# IEEE_EXT_Base.net
KiCad netlist of a schematic drawn in EAGLE
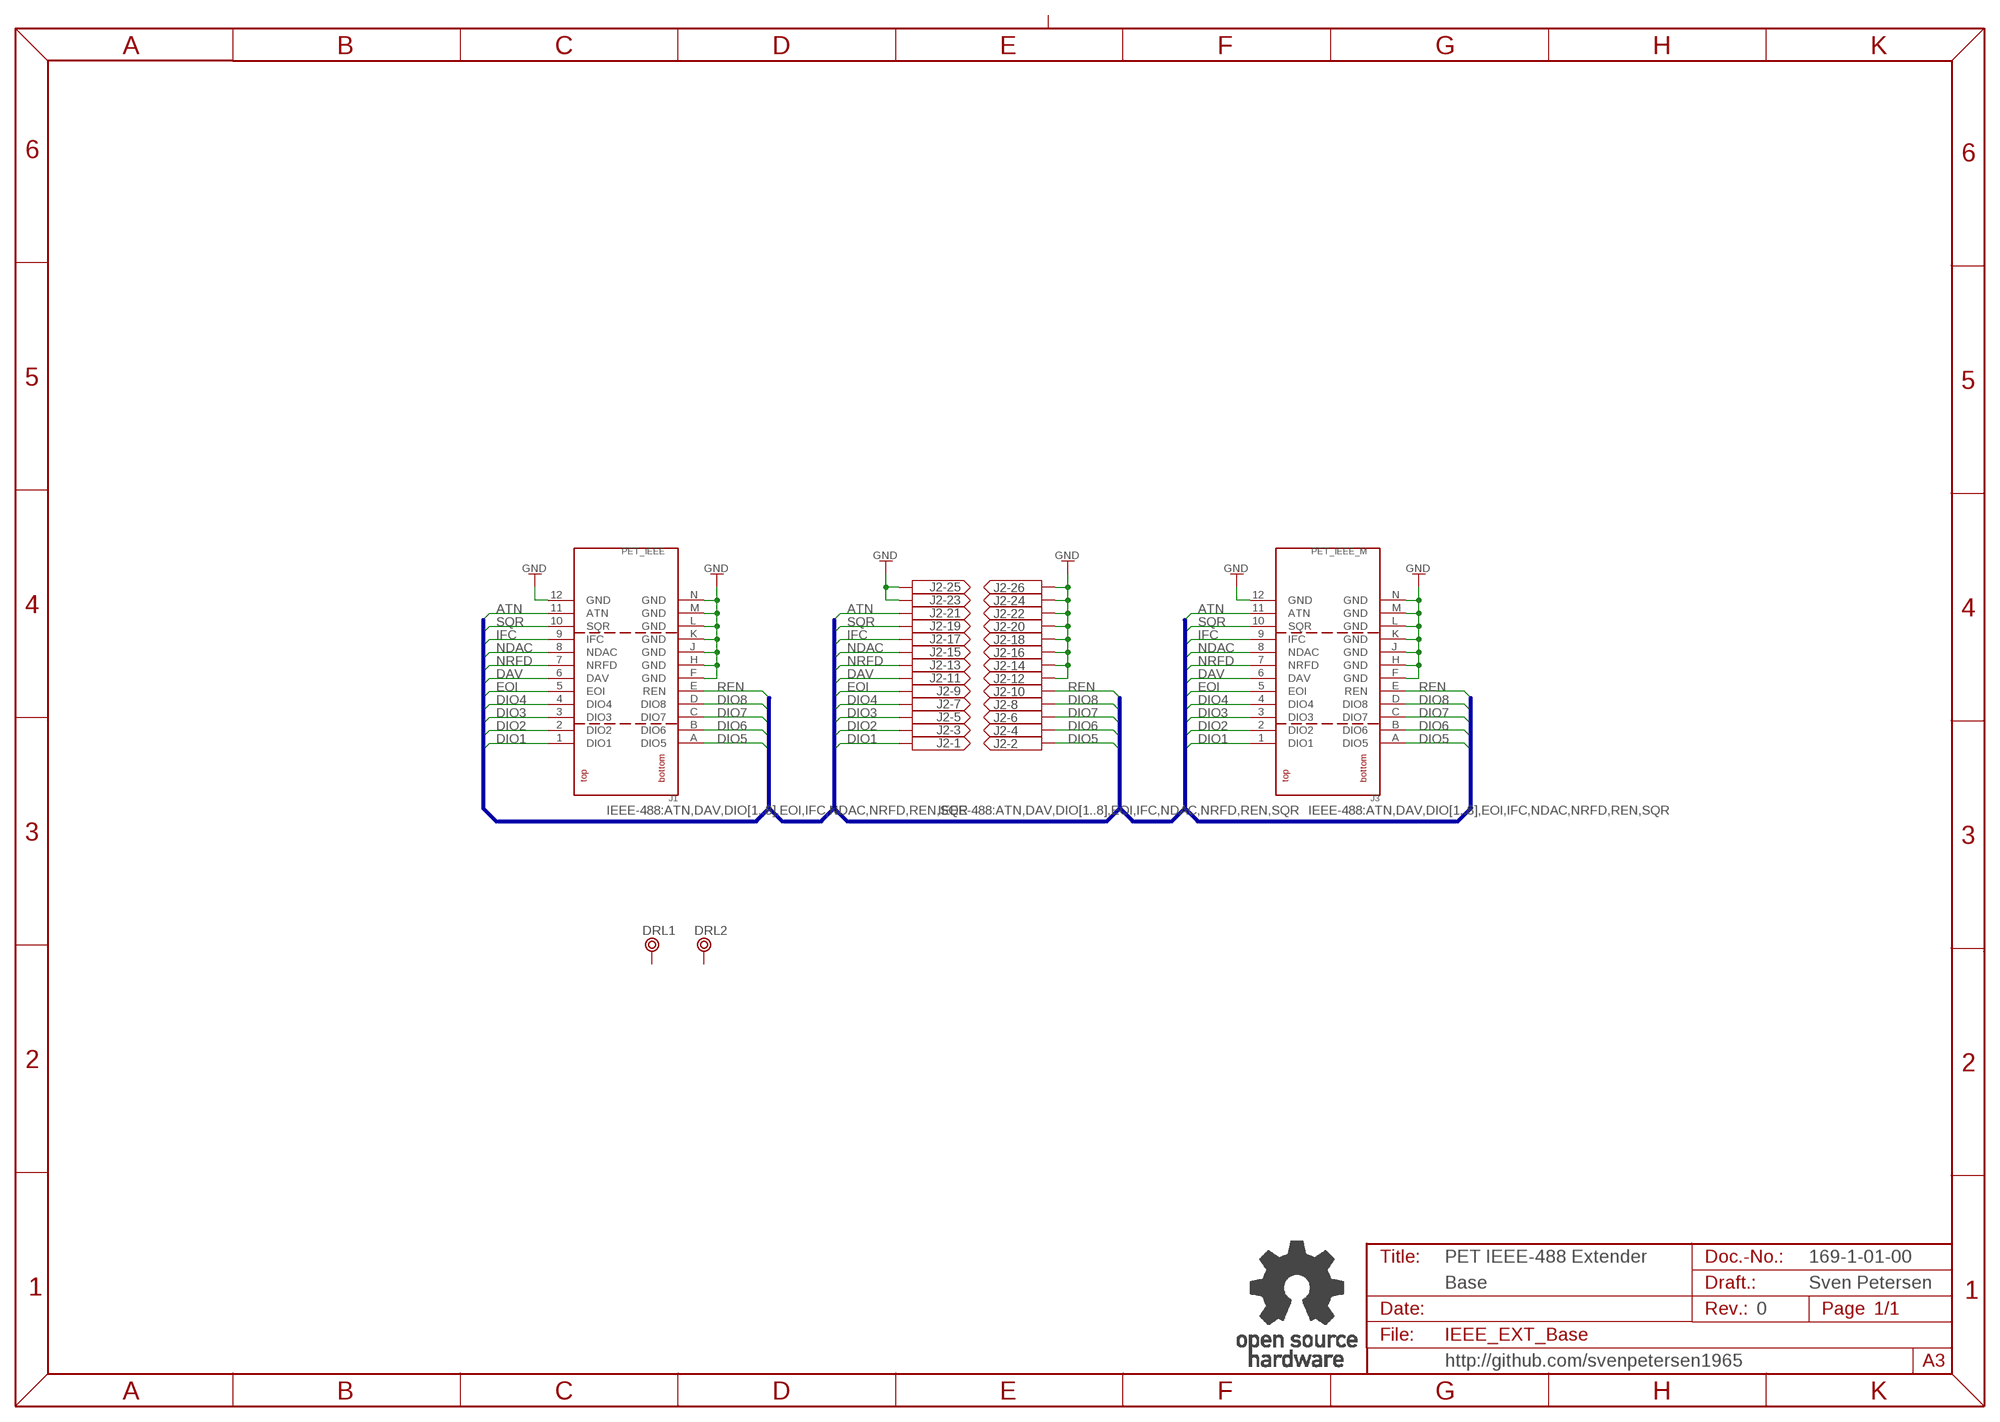
[diagram p0: schematic, sheet 1]

(export (version "E")
  (design (tool "Eeschema 10.0.6"))
  (components
    (comp (ref "DRL1")
      (value "BOHR3,5")
      (footprint "eagle-import:BOHR3,5")
      (libsource (lib "eagle-import") (part "BOHR3,5"))
    )
    (comp (ref "DRL2")
      (value "BOHR3,5")
      (footprint "eagle-import:BOHR3,5")
      (libsource (lib "eagle-import") (part "BOHR3,5"))
    )
    (comp (ref "J1")
      (value "PET_IEEE")
      (footprint "eagle-import:USERPORT")
      (libsource (lib "eagle-import") (part "PET_IEEE"))
    )
    (comp (ref "J2")
      (value "2X13WANNE")
      (footprint "eagle-import:2X13WV")
      (libsource (lib "eagle-import") (part "2X13WANNE"))
    )
    (comp (ref "J3")
      (value "PET_IEEE_M")
      (footprint "eagle-import:PET_IEEE_M")
      (libsource (lib "eagle-import") (part "PET_IEEE_M"))
    )
    (comp (ref "U$9")
      (value "OPEN_SOURCE_HW")
      (footprint "eagle-import:OPENHW")
      (libsource (lib "eagle-import") (part "OPEN_SOURCE_HW"))
    )
  )
  (nets
    (net (code "2") (name "/ATN") (class "Default")
      (node (ref "J1") (pin "11") (pinfunction "ATN_11") (pintype "output"))
      (node (ref "J2") (pin "21") (pinfunction "1_21") (pintype "bidirectional"))
      (node (ref "J3") (pin "11") (pinfunction "ATN_11") (pintype "output"))
    )
    (net (code "3") (name "/DAV") (class "Default")
      (node (ref "J1") (pin "6") (pinfunction "DAV_6") (pintype "bidirectional"))
      (node (ref "J2") (pin "11") (pinfunction "1_11") (pintype "bidirectional"))
      (node (ref "J3") (pin "6") (pinfunction "DAV_6") (pintype "bidirectional"))
    )
    (net (code "4") (name "/DIO1") (class "Default")
      (node (ref "J1") (pin "1") (pinfunction "DIO1_1") (pintype "bidirectional"))
      (node (ref "J2") (pin "1") (pinfunction "1_1") (pintype "bidirectional"))
      (node (ref "J3") (pin "1") (pinfunction "DIO1_1") (pintype "bidirectional"))
    )
    (net (code "5") (name "/DIO2") (class "Default")
      (node (ref "J1") (pin "2") (pinfunction "DIO2_2") (pintype "bidirectional"))
      (node (ref "J2") (pin "3") (pinfunction "1_3") (pintype "bidirectional"))
      (node (ref "J3") (pin "2") (pinfunction "DIO2_2") (pintype "bidirectional"))
    )
    (net (code "6") (name "/DIO3") (class "Default")
      (node (ref "J1") (pin "3") (pinfunction "DIO3_3") (pintype "bidirectional"))
      (node (ref "J2") (pin "5") (pinfunction "1_5") (pintype "bidirectional"))
      (node (ref "J3") (pin "3") (pinfunction "DIO3_3") (pintype "bidirectional"))
    )
    (net (code "7") (name "/DIO4") (class "Default")
      (node (ref "J1") (pin "4") (pinfunction "DIO4_4") (pintype "bidirectional"))
      (node (ref "J2") (pin "7") (pinfunction "1_7") (pintype "bidirectional"))
      (node (ref "J3") (pin "4") (pinfunction "DIO4_4") (pintype "bidirectional"))
    )
    (net (code "8") (name "/DIO5") (class "Default")
      (node (ref "J1") (pin "A") (pinfunction "DIO5_A") (pintype "bidirectional"))
      (node (ref "J2") (pin "2") (pinfunction "1_2") (pintype "bidirectional"))
      (node (ref "J3") (pin "A") (pinfunction "DIO5_A") (pintype "bidirectional"))
    )
    (net (code "9") (name "/DIO6") (class "Default")
      (node (ref "J1") (pin "B") (pinfunction "DIO6_B") (pintype "bidirectional"))
      (node (ref "J2") (pin "4") (pinfunction "1_4") (pintype "bidirectional"))
      (node (ref "J3") (pin "B") (pinfunction "DIO6_B") (pintype "bidirectional"))
    )
    (net (code "10") (name "/DIO7") (class "Default")
      (node (ref "J1") (pin "C") (pinfunction "DIO7_C") (pintype "bidirectional"))
      (node (ref "J2") (pin "6") (pinfunction "1_6") (pintype "bidirectional"))
      (node (ref "J3") (pin "C") (pinfunction "DIO7_C") (pintype "bidirectional"))
    )
    (net (code "11") (name "/DIO8") (class "Default")
      (node (ref "J1") (pin "D") (pinfunction "DIO8_D") (pintype "bidirectional"))
      (node (ref "J2") (pin "8") (pinfunction "1_8") (pintype "bidirectional"))
      (node (ref "J3") (pin "D") (pinfunction "DIO8_D") (pintype "bidirectional"))
    )
    (net (code "12") (name "/EOI") (class "Default")
      (node (ref "J1") (pin "5") (pinfunction "EOI_5") (pintype "input"))
      (node (ref "J2") (pin "9") (pinfunction "1_9") (pintype "bidirectional"))
      (node (ref "J3") (pin "5") (pinfunction "EOI_5") (pintype "input"))
    )
    (net (code "13") (name "/IFC") (class "Default")
      (node (ref "J1") (pin "9") (pinfunction "IFC_9") (pintype "bidirectional"))
      (node (ref "J2") (pin "17") (pinfunction "1_17") (pintype "bidirectional"))
      (node (ref "J3") (pin "9") (pinfunction "IFC_9") (pintype "bidirectional"))
    )
    (net (code "14") (name "/NDAC") (class "Default")
      (node (ref "J1") (pin "8") (pinfunction "NDAC_8") (pintype "bidirectional"))
      (node (ref "J2") (pin "15") (pinfunction "1_15") (pintype "bidirectional"))
      (node (ref "J3") (pin "8") (pinfunction "NDAC_8") (pintype "bidirectional"))
    )
    (net (code "15") (name "/NRFD") (class "Default")
      (node (ref "J1") (pin "7") (pinfunction "NRFD_7") (pintype "bidirectional"))
      (node (ref "J2") (pin "13") (pinfunction "1_13") (pintype "bidirectional"))
      (node (ref "J3") (pin "7") (pinfunction "NRFD_7") (pintype "bidirectional"))
    )
    (net (code "16") (name "/REN") (class "Default")
      (node (ref "J1") (pin "E") (pinfunction "REN_E") (pintype "bidirectional"))
      (node (ref "J2") (pin "10") (pinfunction "1_10") (pintype "bidirectional"))
      (node (ref "J3") (pin "E") (pinfunction "REN_E") (pintype "bidirectional"))
    )
    (net (code "17") (name "/SQR") (class "Default")
      (node (ref "J1") (pin "10") (pinfunction "SQR_10") (pintype "bidirectional"))
      (node (ref "J2") (pin "19") (pinfunction "1_19") (pintype "bidirectional"))
      (node (ref "J3") (pin "10") (pinfunction "SQR_10") (pintype "bidirectional"))
    )
    (net (code "19") (name "GND") (class "Default")
      (node (ref "J1") (pin "12") (pinfunction "GND_12") (pintype "power_in"))
      (node (ref "J1") (pin "F") (pinfunction "GND_F") (pintype "power_in"))
      (node (ref "J1") (pin "H") (pinfunction "GND_H") (pintype "power_in"))
      (node (ref "J1") (pin "J") (pinfunction "GND_J") (pintype "power_in"))
      (node (ref "J1") (pin "K") (pinfunction "GND_K") (pintype "power_in"))
      (node (ref "J1") (pin "L") (pinfunction "GND_L") (pintype "power_in"))
      (node (ref "J1") (pin "M") (pinfunction "GND_M") (pintype "power_in"))
      (node (ref "J1") (pin "N") (pinfunction "GND_N") (pintype "power_in"))
      (node (ref "J2") (pin "12") (pinfunction "1_12") (pintype "bidirectional"))
      (node (ref "J2") (pin "14") (pinfunction "1_14") (pintype "bidirectional"))
      (node (ref "J2") (pin "16") (pinfunction "1_16") (pintype "bidirectional"))
      (node (ref "J2") (pin "18") (pinfunction "1_18") (pintype "bidirectional"))
      (node (ref "J2") (pin "20") (pinfunction "1_20") (pintype "bidirectional"))
      (node (ref "J2") (pin "22") (pinfunction "1_22") (pintype "bidirectional"))
      (node (ref "J2") (pin "23") (pinfunction "1_23") (pintype "bidirectional"))
      (node (ref "J2") (pin "24") (pinfunction "1_24") (pintype "bidirectional"))
      (node (ref "J2") (pin "25") (pinfunction "1_25") (pintype "bidirectional"))
      (node (ref "J2") (pin "26") (pinfunction "1_26") (pintype "bidirectional"))
      (node (ref "J3") (pin "12") (pinfunction "GND_12") (pintype "power_in"))
      (node (ref "J3") (pin "F") (pinfunction "GND_F") (pintype "power_in"))
      (node (ref "J3") (pin "H") (pinfunction "GND_H") (pintype "power_in"))
      (node (ref "J3") (pin "J") (pinfunction "GND_J") (pintype "power_in"))
      (node (ref "J3") (pin "K") (pinfunction "GND_K") (pintype "power_in"))
      (node (ref "J3") (pin "L") (pinfunction "GND_L") (pintype "power_in"))
      (node (ref "J3") (pin "M") (pinfunction "GND_M") (pintype "power_in"))
      (node (ref "J3") (pin "N") (pinfunction "GND_N") (pintype "power_in"))
    )
    (net (code "20") (name "unconnected-(DRL1-PadP$1)") (class "Default")
      (node (ref "DRL1") (pin "P$1") (pinfunction "P$1_P$1") (pintype "passive"))
    )
    (net (code "21") (name "unconnected-(DRL2-PadP$1)") (class "Default")
      (node (ref "DRL2") (pin "P$1") (pinfunction "P$1_P$1") (pintype "passive"))
    )
  )
)
